# PCB_USB_Pwr_Module.net
KiCad netlist of a schematic drawn in EAGLE
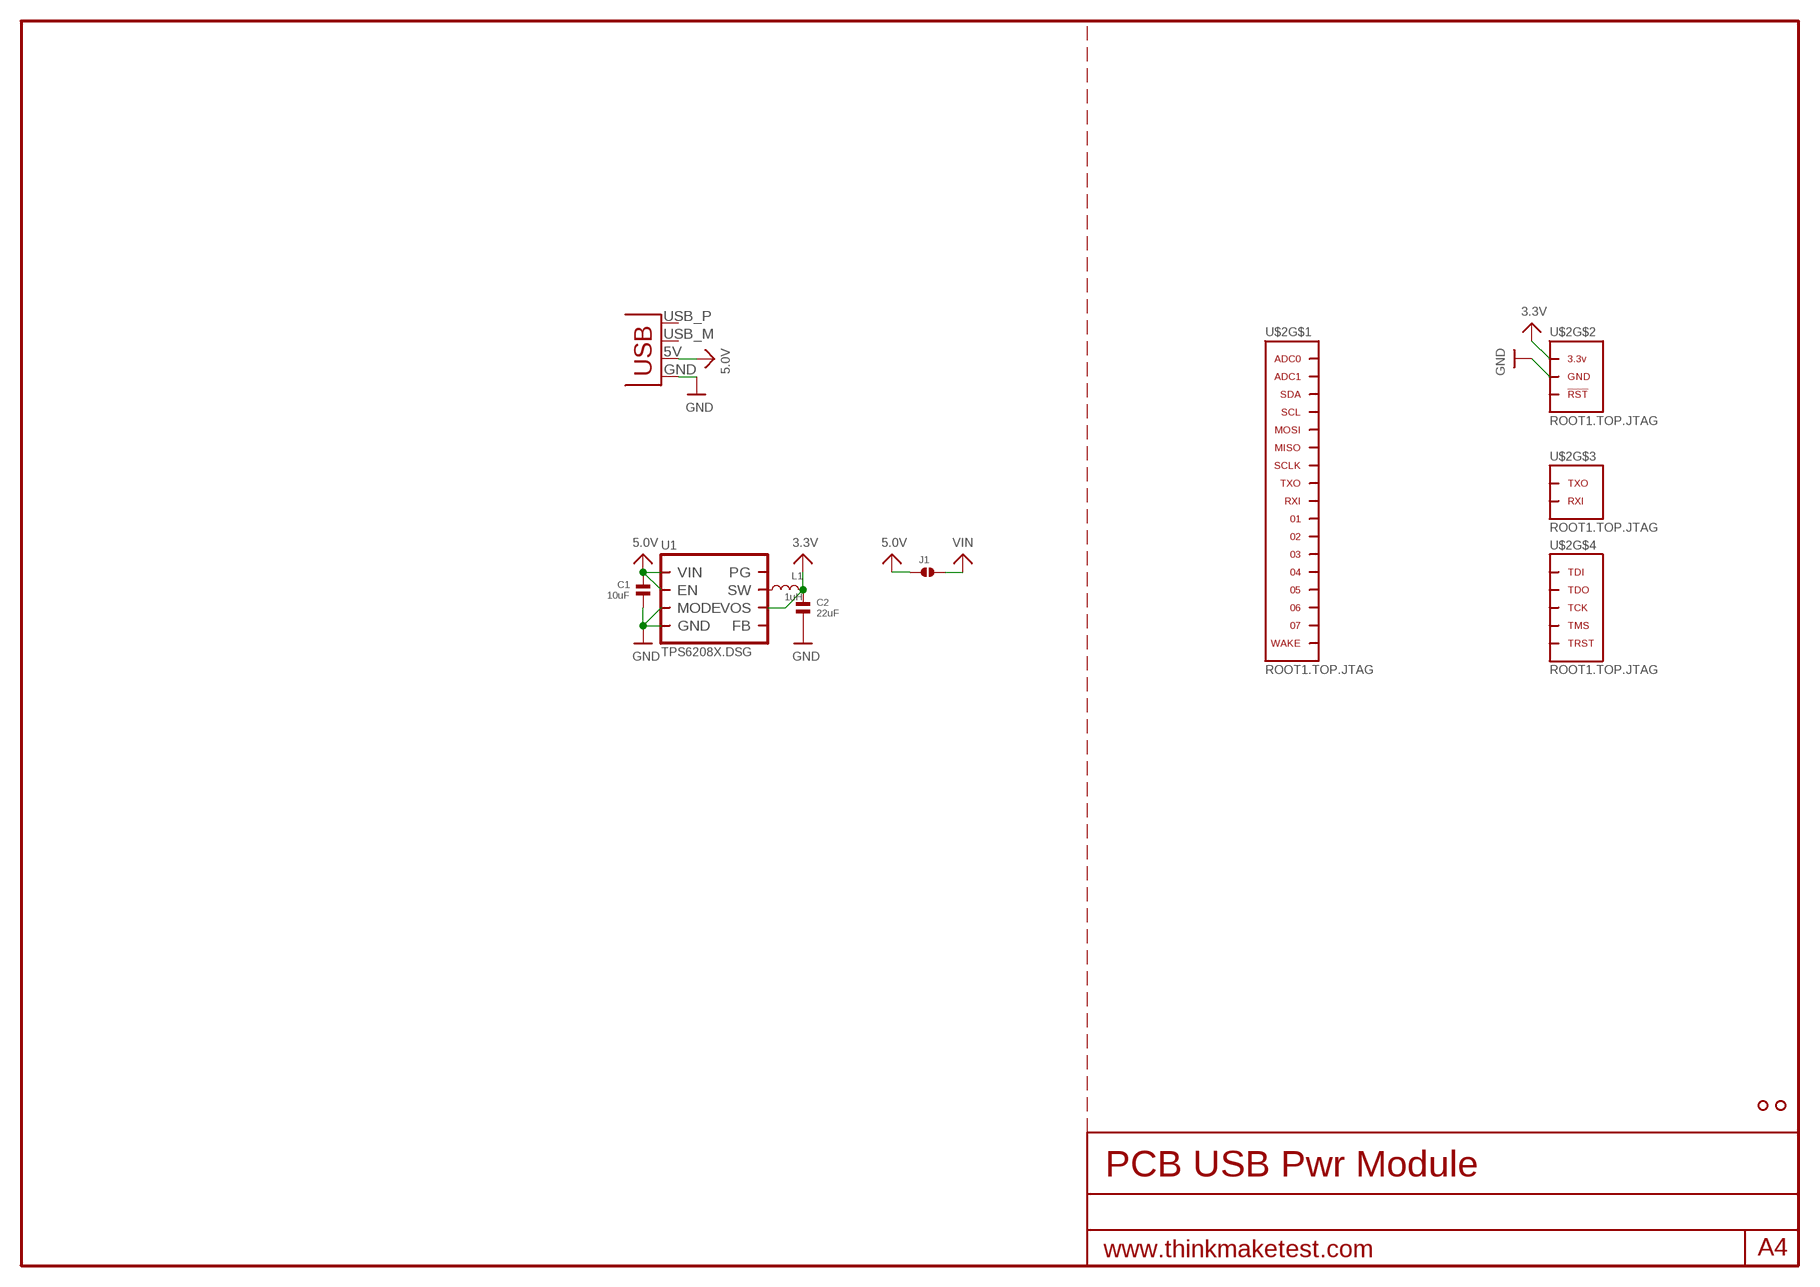
[diagram p0: schematic, sheet 1]

(export (version "E")
  (design (tool "Eeschema 10.0.6"))
  (components
    (comp (ref "C1")
      (value "10uF")
      (footprint "eagle-import:0603")
      (libsource (lib "eagle-import") (part "CAPACITOR.0603"))
    )
    (comp (ref "C2")
      (value "22uF")
      (footprint "eagle-import:0805")
      (libsource (lib "eagle-import") (part "CAPACITOR.0805"))
    )
    (comp (ref "J1")
      (value "SOLDERJUMPER.2.LRG.PASTE")
      (footprint "eagle-import:2.LRG.PASTE")
      (libsource (lib "eagle-import") (part "SOLDERJUMPER.2.LRG.PASTE"))
    )
    (comp (ref "JP1")
      (value "USBPCB")
      (footprint "eagle-import:USB-A-PCB")
      (libsource (lib "eagle-import") (part "USBPCB"))
    )
    (comp (ref "L1")
      (value "1uH")
      (footprint "eagle-import:SRN3015")
      (libsource (lib "eagle-import") (part "INDUCTOR-SRN3015"))
    )
    (comp (ref "U$2")
      (value "ROOT1.TOP.JTAG")
      (footprint "eagle-import:ROOT1.TOP")
      (libsource (lib "eagle-import") (part "ROOT1.TOP.JTAG"))
    )
    (comp (ref "U$3")
      (value "HOLE.#2")
      (footprint "eagle-import:#2")
      (libsource (lib "eagle-import") (part "HOLE.#2"))
    )
    (comp (ref "U$4")
      (value "HOLE.#2")
      (footprint "eagle-import:#2")
      (libsource (lib "eagle-import") (part "HOLE.#2"))
    )
    (comp (ref "U1")
      (value "TPS6208X.DSG")
      (footprint "eagle-import:DSG")
      (libsource (lib "eagle-import") (part "TPS6208X.DSG"))
    )
  )
  (nets
    (net (code "1") (name "3.3V") (class "Default")
      (node (ref "C2") (pin "1") (pinfunction "1_1") (pintype "bidirectional"))
      (node (ref "L1") (pin "1") (pinfunction "1_1") (pintype "passive"))
      (node (ref "U$2") (pin "3.3V@1") (pinfunction "3.3V_3.3V@1") (pintype "bidirectional"))
      (node (ref "U$2") (pin "3.3V@10") (pinfunction "3.3V_3.3V@10") (pintype "bidirectional"))
      (node (ref "U$2") (pin "3.3V@11") (pinfunction "3.3V_3.3V@11") (pintype "bidirectional"))
      (node (ref "U$2") (pin "3.3V@12") (pinfunction "3.3V_3.3V@12") (pintype "bidirectional"))
      (node (ref "U$2") (pin "3.3V@2") (pinfunction "3.3V_3.3V@2") (pintype "bidirectional"))
      (node (ref "U$2") (pin "3.3V@3") (pinfunction "3.3V_3.3V@3") (pintype "bidirectional"))
      (node (ref "U$2") (pin "3.3V@4") (pinfunction "3.3V_3.3V@4") (pintype "bidirectional"))
      (node (ref "U$2") (pin "3.3V@5") (pinfunction "3.3V_3.3V@5") (pintype "bidirectional"))
      (node (ref "U$2") (pin "3.3V@6") (pinfunction "3.3V_3.3V@6") (pintype "bidirectional"))
      (node (ref "U$2") (pin "3.3V@7") (pinfunction "3.3V_3.3V@7") (pintype "bidirectional"))
      (node (ref "U$2") (pin "3.3V@8") (pinfunction "3.3V_3.3V@8") (pintype "bidirectional"))
      (node (ref "U$2") (pin "3.3V@9") (pinfunction "3.3V_3.3V@9") (pintype "bidirectional"))
      (node (ref "U1") (pin "5") (pinfunction "VOS_5") (pintype "bidirectional"))
    )
    (net (code "2") (name "5.0V") (class "Default")
      (node (ref "C1") (pin "1") (pinfunction "1_1") (pintype "bidirectional"))
      (node (ref "J1") (pin "1") (pinfunction "1_1") (pintype "bidirectional"))
      (node (ref "JP1") (pin "5V") (pinfunction "VBUS_5V") (pintype "bidirectional"))
      (node (ref "U1") (pin "1") (pinfunction "EN_1") (pintype "bidirectional"))
      (node (ref "U1") (pin "8") (pinfunction "VIN_8") (pintype "bidirectional"))
    )
    (net (code "3") (name "GND") (class "Default")
      (node (ref "C1") (pin "2") (pinfunction "2_2") (pintype "bidirectional"))
      (node (ref "C2") (pin "2") (pinfunction "2_2") (pintype "bidirectional"))
      (node (ref "JP1") (pin "GND") (pinfunction "GND_GND") (pintype "bidirectional"))
      (node (ref "U$2") (pin "GND@1") (pinfunction "GND_GND@1") (pintype "bidirectional"))
      (node (ref "U$2") (pin "GND@10") (pinfunction "GND_GND@10") (pintype "bidirectional"))
      (node (ref "U$2") (pin "GND@11") (pinfunction "GND_GND@11") (pintype "bidirectional"))
      (node (ref "U$2") (pin "GND@12") (pinfunction "GND_GND@12") (pintype "bidirectional"))
      (node (ref "U$2") (pin "GND@13") (pinfunction "GND_GND@13") (pintype "bidirectional"))
      (node (ref "U$2") (pin "GND@2") (pinfunction "GND_GND@2") (pintype "bidirectional"))
      (node (ref "U$2") (pin "GND@3") (pinfunction "GND_GND@3") (pintype "bidirectional"))
      (node (ref "U$2") (pin "GND@4") (pinfunction "GND_GND@4") (pintype "bidirectional"))
      (node (ref "U$2") (pin "GND@5") (pinfunction "GND_GND@5") (pintype "bidirectional"))
      (node (ref "U$2") (pin "GND@6") (pinfunction "GND_GND@6") (pintype "bidirectional"))
      (node (ref "U$2") (pin "GND@7") (pinfunction "GND_GND@7") (pintype "bidirectional"))
      (node (ref "U$2") (pin "GND@8") (pinfunction "GND_GND@8") (pintype "bidirectional"))
      (node (ref "U$2") (pin "GND@9") (pinfunction "GND_GND@9") (pintype "bidirectional"))
      (node (ref "U1") (pin "2") (pinfunction "GND_2") (pintype "bidirectional"))
      (node (ref "U1") (pin "3") (pinfunction "MODE_3") (pintype "bidirectional"))
      (node (ref "U1") (pin "PAD") (pinfunction "GND_PAD") (pintype "bidirectional"))
    )
    (net (code "4") (name "Net-(U1-SW)") (class "Default")
      (node (ref "L1") (pin "2") (pinfunction "2_2") (pintype "passive"))
      (node (ref "U1") (pin "7") (pinfunction "SW_7") (pintype "bidirectional"))
    )
    (net (code "5") (name "VIN") (class "Default")
      (node (ref "J1") (pin "2") (pinfunction "2_2") (pintype "bidirectional"))
    )
    (net (code "6") (name "unconnected-(JP1-D+-PadUSB_P)") (class "Default")
      (node (ref "JP1") (pin "USB_P") (pinfunction "D+_USB_P") (pintype "bidirectional"))
    )
    (net (code "7") (name "unconnected-(JP1-D--PadUSB_M)") (class "Default")
      (node (ref "JP1") (pin "USB_M") (pinfunction "D-_USB_M") (pintype "bidirectional"))
    )
    (net (code "8") (name "unconnected-(U$2-Pad01)") (class "Default")
      (node (ref "U$2") (pin "01") (pinfunction "01_01") (pintype "bidirectional"))
    )
    (net (code "9") (name "unconnected-(U$2-Pad02)") (class "Default")
      (node (ref "U$2") (pin "02") (pinfunction "02_02") (pintype "bidirectional"))
    )
    (net (code "10") (name "unconnected-(U$2-Pad03)") (class "Default")
      (node (ref "U$2") (pin "03") (pinfunction "03_03") (pintype "bidirectional"))
    )
    (net (code "11") (name "unconnected-(U$2-Pad04)") (class "Default")
      (node (ref "U$2") (pin "04") (pinfunction "04_04") (pintype "bidirectional"))
    )
    (net (code "12") (name "unconnected-(U$2-Pad05)") (class "Default")
      (node (ref "U$2") (pin "05") (pinfunction "05_05") (pintype "bidirectional"))
    )
    (net (code "13") (name "unconnected-(U$2-Pad06)") (class "Default")
      (node (ref "U$2") (pin "06") (pinfunction "06_06") (pintype "bidirectional"))
    )
    (net (code "14") (name "unconnected-(U$2-Pad07)") (class "Default")
      (node (ref "U$2") (pin "07") (pinfunction "07_07") (pintype "bidirectional"))
    )
    (net (code "15") (name "unconnected-(U$2-PadADC0)") (class "Default")
      (node (ref "U$2") (pin "ADC0") (pinfunction "ADC0_ADC0") (pintype "bidirectional"))
    )
    (net (code "16") (name "unconnected-(U$2-PadADC1)") (class "Default")
      (node (ref "U$2") (pin "ADC1") (pinfunction "ADC1_ADC1") (pintype "bidirectional"))
    )
    (net (code "17") (name "unconnected-(U$2-PadMISO)") (class "Default")
      (node (ref "U$2") (pin "MISO") (pinfunction "MISO_MISO") (pintype "bidirectional"))
    )
    (net (code "18") (name "unconnected-(U$2-PadMOSI)") (class "Default")
      (node (ref "U$2") (pin "MOSI") (pinfunction "MOSI_MOSI") (pintype "bidirectional"))
    )
    (net (code "19") (name "unconnected-(U$2-PadRXI)") (class "Default")
      (node (ref "U$2") (pin "RXI") (pinfunction "RXI_RXI") (pintype "bidirectional"))
    )
    (net (code "20") (name "unconnected-(U$2-PadSCL)") (class "Default")
      (node (ref "U$2") (pin "SCL") (pinfunction "SCL_SCL") (pintype "bidirectional"))
    )
    (net (code "21") (name "unconnected-(U$2-PadSCLK)") (class "Default")
      (node (ref "U$2") (pin "SCLK") (pinfunction "SCLK_SCLK") (pintype "bidirectional"))
    )
    (net (code "22") (name "unconnected-(U$2-PadSDA)") (class "Default")
      (node (ref "U$2") (pin "SDA") (pinfunction "SDA_SDA") (pintype "bidirectional"))
    )
    (net (code "23") (name "unconnected-(U$2-PadTCK)") (class "Default")
      (node (ref "U$2") (pin "TCK") (pinfunction "TCK_TCK") (pintype "bidirectional"))
    )
    (net (code "24") (name "unconnected-(U$2-PadTDI)") (class "Default")
      (node (ref "U$2") (pin "TDI") (pinfunction "TDI_TDI") (pintype "bidirectional"))
    )
    (net (code "25") (name "unconnected-(U$2-PadTDO)") (class "Default")
      (node (ref "U$2") (pin "TDO") (pinfunction "TDO_TDO") (pintype "bidirectional"))
    )
    (net (code "26") (name "unconnected-(U$2-PadTMS)") (class "Default")
      (node (ref "U$2") (pin "TMS") (pinfunction "TMS_TMS") (pintype "bidirectional"))
    )
    (net (code "27") (name "unconnected-(U$2-PadTRST)") (class "Default")
      (node (ref "U$2") (pin "TRST") (pinfunction "TRST_TRST") (pintype "bidirectional"))
    )
    (net (code "28") (name "unconnected-(U$2-PadTXO)") (class "Default")
      (node (ref "U$2") (pin "TXO") (pinfunction "TXO_TXO") (pintype "bidirectional"))
    )
    (net (code "29") (name "unconnected-(U$2-PadWAKE)") (class "Default")
      (node (ref "U$2") (pin "WAKE") (pinfunction "WAKE_WAKE") (pintype "bidirectional"))
    )
    (net (code "30") (name "unconnected-(U$2B-~{RST}-PadRST)") (class "Default")
      (node (ref "U$2") (pin "RST") (pinfunction "~{RST}_RST") (pintype "bidirectional"))
    )
    (net (code "31") (name "unconnected-(U$2C-RXI-PadRXI.DBG)") (class "Default")
      (node (ref "U$2") (pin "RXI.DBG") (pinfunction "RXI_RXI.DBG") (pintype "bidirectional"))
    )
    (net (code "32") (name "unconnected-(U$2C-TXO-PadTXO.DBG)") (class "Default")
      (node (ref "U$2") (pin "TXO.DBG") (pinfunction "TXO_TXO.DBG") (pintype "bidirectional"))
    )
    (net (code "33") (name "unconnected-(U1-FB-Pad4)") (class "Default")
      (node (ref "U1") (pin "4") (pinfunction "FB_4") (pintype "bidirectional"))
    )
    (net (code "34") (name "unconnected-(U1-PG-Pad6)") (class "Default")
      (node (ref "U1") (pin "6") (pinfunction "PG_6") (pintype "bidirectional"))
    )
  )
)
